# reefingBrd.net
KiCad netlist of a schematic drawn in EAGLE
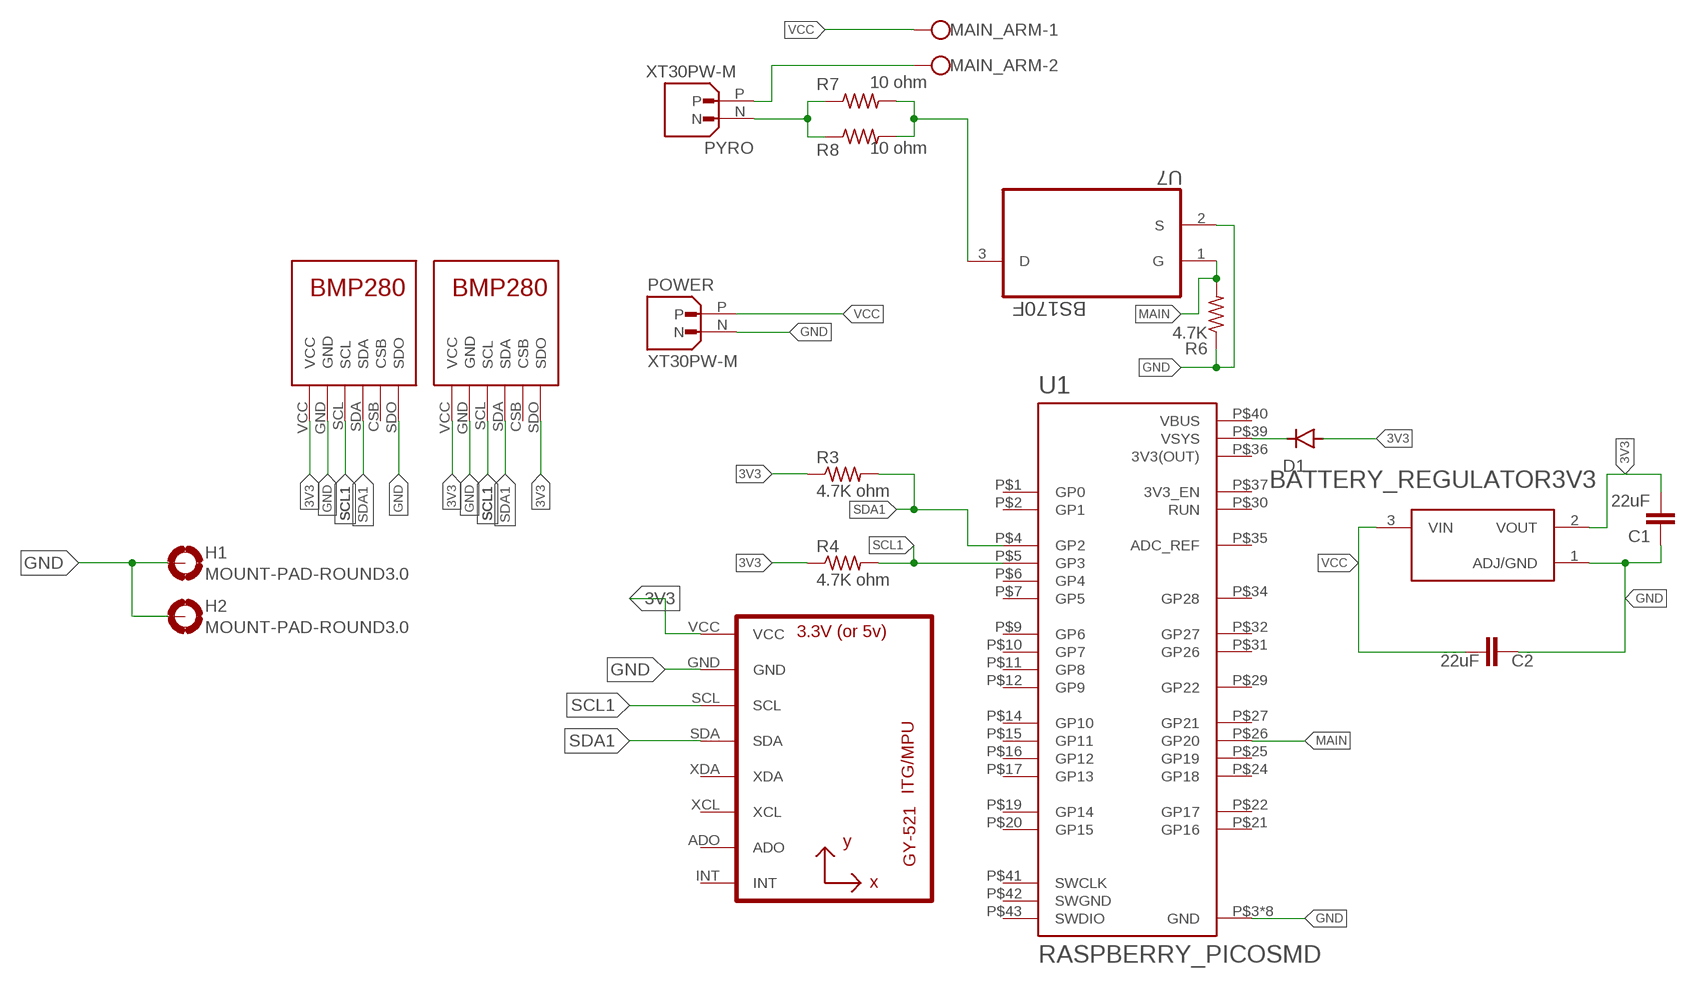
[diagram p0: schematic, sheet 1]

(export (version "E")
  (design (tool "Eeschema 10.0.6"))
  (components
    (comp (ref "BATTERY_REGULATOR3V3")
      (value "AMS1117-3.3")
      (footprint "eagle-import:SOT229P700X180-4N")
      (fields (field (name "MF") "Advanced Monolithic Systems"))
      (libsource (lib "eagle-import") (part "AMS1117-3.3"))
    )
    (comp (ref "C1")
      (value "22uF")
      (footprint "eagle-import:0805")
      (libsource (lib "eagle-import") (part "22UF-0805-6.3V-20%"))
    )
    (comp (ref "C2")
      (value "22uF")
      (footprint "eagle-import:0805")
      (libsource (lib "eagle-import") (part "22UF-0805-6.3V-20%"))
    )
    (comp (ref "D1")
      (value "1N4004")
      (footprint "eagle-import:DO41-10")
      (libsource (lib "eagle-import") (part "1N4004"))
    )
    (comp (ref "H1")
      (value "MOUNT-PAD-ROUND3.0")
      (footprint "eagle-import:3,0-PAD")
      (libsource (lib "eagle-import") (part "MOUNT-PAD-ROUND3.0"))
    )
    (comp (ref "H2")
      (value "MOUNT-PAD-ROUND3.0")
      (footprint "eagle-import:3,0-PAD")
      (libsource (lib "eagle-import") (part "MOUNT-PAD-ROUND3.0"))
    )
    (comp (ref "MAIN_ARM")
      (value "W237-102")
      (footprint "eagle-import:W237-102")
      (fields (field (name "MPN") "237-102"))
      (libsource (lib "eagle-import") (part "W237-102"))
    )
    (comp (ref "POWER")
      (value "XT30PW-M")
      (footprint "eagle-import:AMASS_XT30PW-M")
      (fields (field (name "MF") "AMASS"))
      (libsource (lib "eagle-import") (part "XT30PW-M"))
    )
    (comp (ref "PYRO")
      (value "XT30PW-M")
      (footprint "eagle-import:AMASS_XT30PW-M")
      (fields (field (name "MF") "AMASS"))
      (libsource (lib "eagle-import") (part "XT30PW-M"))
    )
    (comp (ref "R3")
      (value "4.7K ohm")
      (footprint "eagle-import:R0805")
      (libsource (lib "eagle-import") (part "R-US_R0805"))
    )
    (comp (ref "R4")
      (value "4.7K ohm")
      (footprint "eagle-import:R0805")
      (libsource (lib "eagle-import") (part "R-US_R0805"))
    )
    (comp (ref "R6")
      (value "4.7K")
      (footprint "eagle-import:R0805")
      (libsource (lib "eagle-import") (part "R-US_R0805"))
    )
    (comp (ref "R7")
      (value "10 ohm")
      (footprint "eagle-import:0207_10")
      (libsource (lib "eagle-import") (part "R-US_0207/10"))
    )
    (comp (ref "R8")
      (value "10 ohm")
      (footprint "eagle-import:0207_10")
      (libsource (lib "eagle-import") (part "R-US_0207/10"))
    )
    (comp (ref "U$1")
      (value "BMP280")
      (footprint "eagle-import:BMP280")
      (libsource (lib "eagle-import") (part "BMP280"))
    )
    (comp (ref "U$2")
      (value "BMP280")
      (footprint "eagle-import:BMP280")
      (libsource (lib "eagle-import") (part "BMP280"))
    )
    (comp (ref "U1")
      (value "RASPBERRY_PICOSMD")
      (footprint "eagle-import:PICO-PKG-SMD")
      (libsource (lib "eagle-import") (part "RASPBERRY_PICOSMD"))
    )
    (comp (ref "U2")
      (value "GY-521MPU6050")
      (footprint "eagle-import:GY-521")
      (libsource (lib "eagle-import") (part "GY-521MPU6050"))
    )
    (comp (ref "U7")
      (value "BS170F")
      (footprint "eagle-import:SOT91P240X120-3N")
      (fields (field (name "MF") "Diodes Inc."))
      (libsource (lib "eagle-import") (part "BS170F"))
    )
  )
  (nets
    (net (code "1") (name "/3V3(OUT)") (class "Default")
      (node (ref "U1") (pin "P$36") (pinfunction "3V3(OUT)_P$36") (pintype "power_in"))
    )
    (net (code "2") (name "/SWGND") (class "Default")
      (node (ref "U1") (pin "P$42") (pinfunction "SWGND_P$42") (pintype "power_in"))
    )
    (net (code "3") (name "/VBUS") (class "Default")
      (node (ref "U1") (pin "P$40") (pinfunction "VBUS_P$40") (pintype "power_in"))
    )
    (net (code "4") (name "3V3") (class "Default")
      (node (ref "BATTERY_REGULATOR3V3") (pin "2") (pinfunction "VOUT_2") (pintype "output"))
      (node (ref "C1") (pin "2") (pinfunction "2_2") (pintype "passive"))
      (node (ref "D1") (pin "A") (pinfunction "A_A") (pintype "passive"))
      (node (ref "R3") (pin "1") (pinfunction "1_1") (pintype "passive"))
      (node (ref "R4") (pin "1") (pinfunction "1_1") (pintype "passive"))
      (node (ref "U$1") (pin "VCC") (pinfunction "VCC_VCC") (pintype "bidirectional"))
      (node (ref "U$2") (pin "SDO") (pinfunction "SDO_SDO") (pintype "bidirectional"))
      (node (ref "U$2") (pin "VCC") (pinfunction "VCC_VCC") (pintype "bidirectional"))
      (node (ref "U2") (pin "VCC") (pinfunction "VCC_VCC") (pintype "bidirectional"))
    )
    (net (code "5") (name "GND") (class "Default")
      (node (ref "BATTERY_REGULATOR3V3") (pin "1") (pinfunction "ADJ/GND_1") (pintype "power_in"))
      (node (ref "C1") (pin "1") (pinfunction "1_1") (pintype "passive"))
      (node (ref "C2") (pin "1") (pinfunction "1_1") (pintype "passive"))
      (node (ref "H1") (pin "B3,0") (pinfunction "MOUNT_B3,0") (pintype "passive"))
      (node (ref "H2") (pin "B3,0") (pinfunction "MOUNT_B3,0") (pintype "passive"))
      (node (ref "POWER") (pin "N") (pinfunction "N_N") (pintype "power_in"))
      (node (ref "R6") (pin "1") (pinfunction "1_1") (pintype "passive"))
      (node (ref "U$1") (pin "GND") (pinfunction "GND_GND") (pintype "bidirectional"))
      (node (ref "U$1") (pin "SDO") (pinfunction "SDO_SDO") (pintype "bidirectional"))
      (node (ref "U$2") (pin "GND") (pinfunction "GND_GND") (pintype "bidirectional"))
      (node (ref "U1") (pin "P$13") (pinfunction "GND_P$13") (pintype "power_in"))
      (node (ref "U1") (pin "P$18") (pinfunction "GND_P$18") (pintype "power_in"))
      (node (ref "U1") (pin "P$23") (pinfunction "GND_P$23") (pintype "power_in"))
      (node (ref "U1") (pin "P$28") (pinfunction "GND_P$28") (pintype "power_in"))
      (node (ref "U1") (pin "P$3") (pinfunction "GND_P$3") (pintype "power_in"))
      (node (ref "U1") (pin "P$33") (pinfunction "GND_P$33") (pintype "power_in"))
      (node (ref "U1") (pin "P$38") (pinfunction "GND_P$38") (pintype "power_in"))
      (node (ref "U1") (pin "P$8") (pinfunction "GND_P$8") (pintype "power_in"))
      (node (ref "U2") (pin "GND") (pinfunction "GND_GND") (pintype "bidirectional"))
      (node (ref "U7") (pin "2") (pinfunction "S_2") (pintype "passive"))
    )
    (net (code "6") (name "MAIN") (class "Default")
      (node (ref "R6") (pin "2") (pinfunction "2_2") (pintype "passive"))
      (node (ref "U1") (pin "P$26") (pinfunction "GP20_P$26") (pintype "bidirectional"))
      (node (ref "U7") (pin "1") (pinfunction "G_1") (pintype "passive"))
    )
    (net (code "7") (name "Net-(MAIN_ARMB-KL)") (class "Default")
      (node (ref "MAIN_ARM") (pin "2") (pinfunction "KL_2") (pintype "passive"))
      (node (ref "PYRO") (pin "P") (pinfunction "P_P") (pintype "power_in"))
    )
    (net (code "8") (name "Net-(PYRO-PadN)") (class "Default")
      (node (ref "PYRO") (pin "N") (pinfunction "N_N") (pintype "power_in"))
      (node (ref "R7") (pin "1") (pinfunction "1_1") (pintype "passive"))
      (node (ref "R8") (pin "1") (pinfunction "1_1") (pintype "passive"))
    )
    (net (code "9") (name "Net-(U1-VSYS)") (class "Default")
      (node (ref "D1") (pin "C") (pinfunction "C_C") (pintype "passive"))
      (node (ref "U1") (pin "P$39") (pinfunction "VSYS_P$39") (pintype "power_in"))
    )
    (net (code "10") (name "Net-(U7-D)") (class "Default")
      (node (ref "R7") (pin "2") (pinfunction "2_2") (pintype "passive"))
      (node (ref "R8") (pin "2") (pinfunction "2_2") (pintype "passive"))
      (node (ref "U7") (pin "3") (pinfunction "D_3") (pintype "passive"))
    )
    (net (code "11") (name "SCL1") (class "Default")
      (node (ref "R4") (pin "2") (pinfunction "2_2") (pintype "passive"))
      (node (ref "U$1") (pin "SCL") (pinfunction "SCL_SCL") (pintype "bidirectional"))
      (node (ref "U$2") (pin "SCL") (pinfunction "SCL_SCL") (pintype "bidirectional"))
      (node (ref "U1") (pin "P$5") (pinfunction "GP3_P$5") (pintype "bidirectional"))
      (node (ref "U2") (pin "SCL") (pinfunction "SCL_SCL") (pintype "bidirectional"))
    )
    (net (code "12") (name "SDA1") (class "Default")
      (node (ref "R3") (pin "2") (pinfunction "2_2") (pintype "passive"))
      (node (ref "U$1") (pin "SDA") (pinfunction "SDA_SDA") (pintype "bidirectional"))
      (node (ref "U$2") (pin "SDA") (pinfunction "SDA_SDA") (pintype "bidirectional"))
      (node (ref "U1") (pin "P$4") (pinfunction "GP2_P$4") (pintype "bidirectional"))
      (node (ref "U2") (pin "SDA") (pinfunction "SDA_SDA") (pintype "bidirectional"))
    )
    (net (code "13") (name "VCC") (class "Default")
      (node (ref "BATTERY_REGULATOR3V3") (pin "3") (pinfunction "VIN_3") (pintype "input"))
      (node (ref "C2") (pin "2") (pinfunction "2_2") (pintype "passive"))
      (node (ref "MAIN_ARM") (pin "1") (pinfunction "KL_1") (pintype "passive"))
      (node (ref "POWER") (pin "P") (pinfunction "P_P") (pintype "power_in"))
    )
    (net (code "14") (name "unconnected-(U$1-PadCSB)") (class "Default")
      (node (ref "U$1") (pin "CSB") (pinfunction "CSB_CSB") (pintype "bidirectional"))
    )
    (net (code "15") (name "unconnected-(U$2-PadCSB)") (class "Default")
      (node (ref "U$2") (pin "CSB") (pinfunction "CSB_CSB") (pintype "bidirectional"))
    )
    (net (code "16") (name "unconnected-(U1-3V3_EN-PadP$37)") (class "Default")
      (node (ref "U1") (pin "P$37") (pinfunction "3V3_EN_P$37") (pintype "input"))
    )
    (net (code "17") (name "unconnected-(U1-ADC_REF-PadP$35)") (class "Default")
      (node (ref "U1") (pin "P$35") (pinfunction "ADC_REF_P$35") (pintype "input"))
    )
    (net (code "18") (name "unconnected-(U1-GP0-PadP$1)") (class "Default")
      (node (ref "U1") (pin "P$1") (pinfunction "GP0_P$1") (pintype "bidirectional"))
    )
    (net (code "19") (name "unconnected-(U1-GP1-PadP$2)") (class "Default")
      (node (ref "U1") (pin "P$2") (pinfunction "GP1_P$2") (pintype "bidirectional"))
    )
    (net (code "20") (name "unconnected-(U1-GP4-PadP$6)") (class "Default")
      (node (ref "U1") (pin "P$6") (pinfunction "GP4_P$6") (pintype "bidirectional"))
    )
    (net (code "21") (name "unconnected-(U1-GP5-PadP$7)") (class "Default")
      (node (ref "U1") (pin "P$7") (pinfunction "GP5_P$7") (pintype "bidirectional"))
    )
    (net (code "22") (name "unconnected-(U1-GP6-PadP$9)") (class "Default")
      (node (ref "U1") (pin "P$9") (pinfunction "GP6_P$9") (pintype "bidirectional"))
    )
    (net (code "23") (name "unconnected-(U1-GP7-PadP$10)") (class "Default")
      (node (ref "U1") (pin "P$10") (pinfunction "GP7_P$10") (pintype "bidirectional"))
    )
    (net (code "24") (name "unconnected-(U1-GP8-PadP$11)") (class "Default")
      (node (ref "U1") (pin "P$11") (pinfunction "GP8_P$11") (pintype "bidirectional"))
    )
    (net (code "25") (name "unconnected-(U1-GP9-PadP$12)") (class "Default")
      (node (ref "U1") (pin "P$12") (pinfunction "GP9_P$12") (pintype "bidirectional"))
    )
    (net (code "26") (name "unconnected-(U1-GP10-PadP$14)") (class "Default")
      (node (ref "U1") (pin "P$14") (pinfunction "GP10_P$14") (pintype "bidirectional"))
    )
    (net (code "27") (name "unconnected-(U1-GP11-PadP$15)") (class "Default")
      (node (ref "U1") (pin "P$15") (pinfunction "GP11_P$15") (pintype "bidirectional"))
    )
    (net (code "28") (name "unconnected-(U1-GP12-PadP$16)") (class "Default")
      (node (ref "U1") (pin "P$16") (pinfunction "GP12_P$16") (pintype "bidirectional"))
    )
    (net (code "29") (name "unconnected-(U1-GP13-PadP$17)") (class "Default")
      (node (ref "U1") (pin "P$17") (pinfunction "GP13_P$17") (pintype "bidirectional"))
    )
    (net (code "30") (name "unconnected-(U1-GP14-PadP$19)") (class "Default")
      (node (ref "U1") (pin "P$19") (pinfunction "GP14_P$19") (pintype "bidirectional"))
    )
    (net (code "31") (name "unconnected-(U1-GP15-PadP$20)") (class "Default")
      (node (ref "U1") (pin "P$20") (pinfunction "GP15_P$20") (pintype "bidirectional"))
    )
    (net (code "32") (name "unconnected-(U1-GP16-PadP$21)") (class "Default")
      (node (ref "U1") (pin "P$21") (pinfunction "GP16_P$21") (pintype "bidirectional"))
    )
    (net (code "33") (name "unconnected-(U1-GP17-PadP$22)") (class "Default")
      (node (ref "U1") (pin "P$22") (pinfunction "GP17_P$22") (pintype "bidirectional"))
    )
    (net (code "34") (name "unconnected-(U1-GP18-PadP$24)") (class "Default")
      (node (ref "U1") (pin "P$24") (pinfunction "GP18_P$24") (pintype "bidirectional"))
    )
    (net (code "35") (name "unconnected-(U1-GP19-PadP$25)") (class "Default")
      (node (ref "U1") (pin "P$25") (pinfunction "GP19_P$25") (pintype "bidirectional"))
    )
    (net (code "36") (name "unconnected-(U1-GP21-PadP$27)") (class "Default")
      (node (ref "U1") (pin "P$27") (pinfunction "GP21_P$27") (pintype "bidirectional"))
    )
    (net (code "37") (name "unconnected-(U1-GP22-PadP$29)") (class "Default")
      (node (ref "U1") (pin "P$29") (pinfunction "GP22_P$29") (pintype "bidirectional"))
    )
    (net (code "38") (name "unconnected-(U1-GP26-PadP$31)") (class "Default")
      (node (ref "U1") (pin "P$31") (pinfunction "GP26_P$31") (pintype "bidirectional"))
    )
    (net (code "39") (name "unconnected-(U1-GP27-PadP$32)") (class "Default")
      (node (ref "U1") (pin "P$32") (pinfunction "GP27_P$32") (pintype "bidirectional"))
    )
    (net (code "40") (name "unconnected-(U1-GP28-PadP$34)") (class "Default")
      (node (ref "U1") (pin "P$34") (pinfunction "GP28_P$34") (pintype "bidirectional"))
    )
    (net (code "41") (name "unconnected-(U1-RUN-PadP$30)") (class "Default")
      (node (ref "U1") (pin "P$30") (pinfunction "RUN_P$30") (pintype "input"))
    )
    (net (code "42") (name "unconnected-(U1-SWCLK-PadP$41)") (class "Default")
      (node (ref "U1") (pin "P$41") (pinfunction "SWCLK_P$41") (pintype "input"))
    )
    (net (code "43") (name "unconnected-(U1-SWDIO-PadP$43)") (class "Default")
      (node (ref "U1") (pin "P$43") (pinfunction "SWDIO_P$43") (pintype "bidirectional"))
    )
    (net (code "44") (name "unconnected-(U2-PadADO)") (class "Default")
      (node (ref "U2") (pin "ADO") (pinfunction "ADO_ADO") (pintype "bidirectional"))
    )
    (net (code "45") (name "unconnected-(U2-PadINT)") (class "Default")
      (node (ref "U2") (pin "INT") (pinfunction "INT_INT") (pintype "bidirectional"))
    )
    (net (code "46") (name "unconnected-(U2-PadXCL)") (class "Default")
      (node (ref "U2") (pin "XCL") (pinfunction "XCL_XCL") (pintype "bidirectional"))
    )
    (net (code "47") (name "unconnected-(U2-PadXDA)") (class "Default")
      (node (ref "U2") (pin "XDA") (pinfunction "XDA_XDA") (pintype "bidirectional"))
    )
  )
)
